# Sheet1.net
KiCad netlist of a schematic drawn in Altium Designer
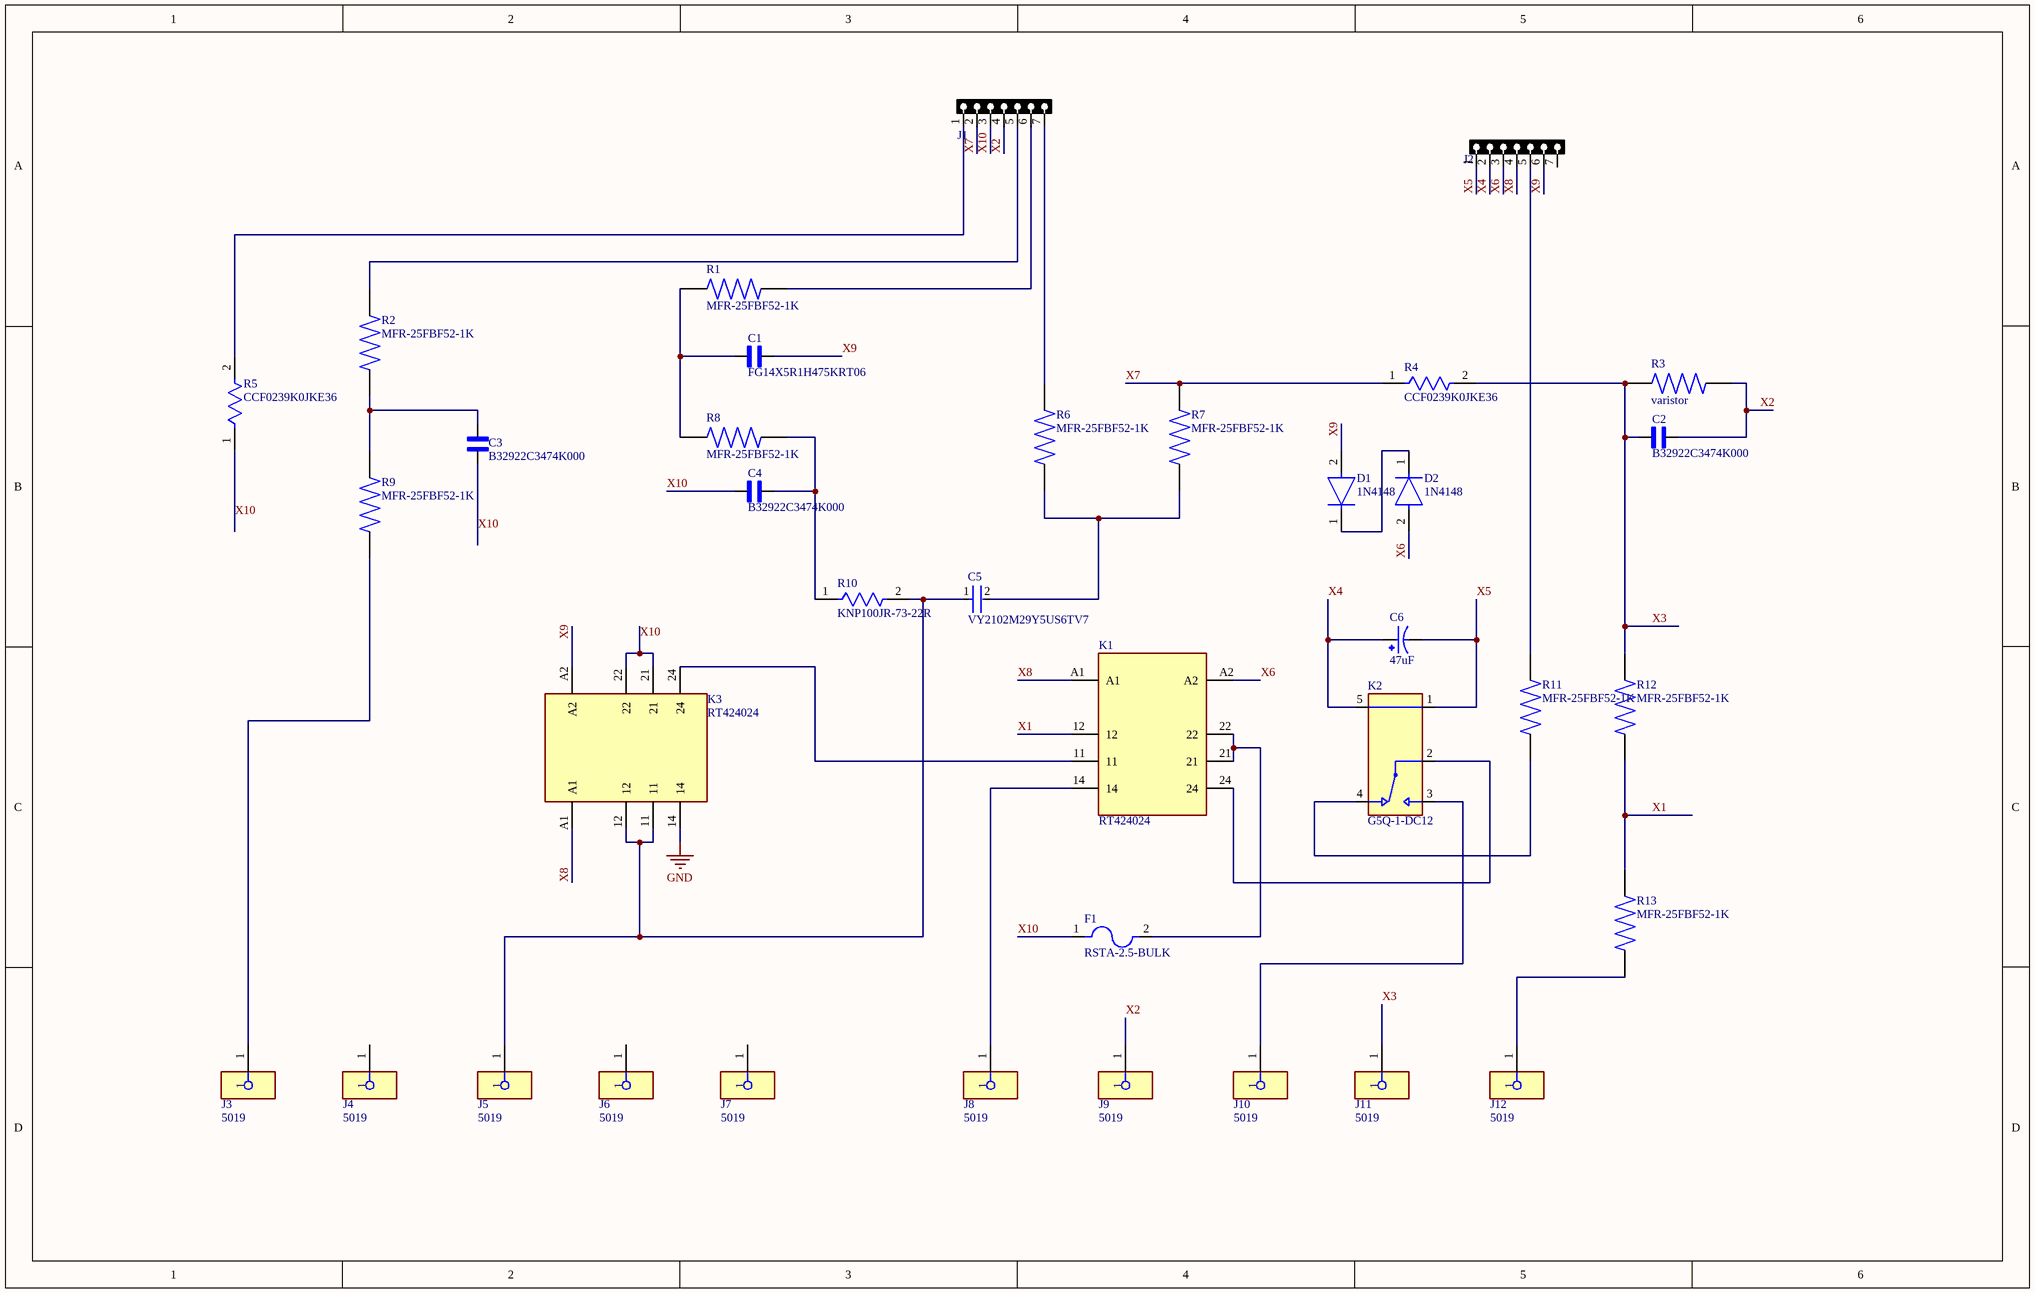
[diagram p0: Sheet1.SchDoc]

(export (version "E")
  (design (tool "Eeschema 10.0.6"))
  (components
    (comp (ref "C1")
      (value "FG14X5R1H475KRT06")
      (footprint "CAPRB250W50L450T300H550")
      (description "4.7 ÂµF Â±10% 50V Ceramic Capacitor X5R Radial")
      (fields (field (name "MF") "TDK"))
      (libsource (lib "FG14X5R1H475KRT06") (part "FG14X5R1H475KRT06"))
    )
    (comp (ref "C2")
      (value "B32922C3474K000")
      (footprint "CAPRR1500W80L1800T900H1750")
      (description "Safety Capacitor, 0.47 uF, 305 VAC, Â± 10%, X2, Metallized PP, Radial Box - 2 Pin, Through Hole")
      (fields (field (name "MF") "TDK"))
      (libsource (lib "") (part "B32922C3474K000_1"))
    )
    (comp (ref "C3")
      (value "B32922C3474K000")
      (footprint "CAPRR1500W80L1800T900H1750")
      (description "Safety Capacitor, 0.47 uF, 305 VAC, Â± 10%, X2, Metallized PP, Radial Box - 2 Pin, Through Hole")
      (fields (field (name "MF") "TDK"))
      (libsource (lib "B32922C3474K000") (part "B32922C3474K000"))
    )
    (comp (ref "C4")
      (value "B32922C3474K000")
      (footprint "CAPRR1500W80L1800T900H1750")
      (description "Safety Capacitor, 0.47 uF, 305 VAC, Â± 10%, X2, Metallized PP, Radial Box - 2 Pin, Through Hole")
      (fields (field (name "MF") "TDK"))
      (libsource (lib "") (part "B32922C3474K000_1"))
    )
    (comp (ref "C5")
      (value "VY2102M29Y5US6TV7")
      (footprint "FP-VY2102M29Y5US6TV7-MFG")
      (fields (field (name "VOLTAGE") "300V") (field (name "TOLERANCE") "20%"))
      (libsource (lib "Altium Content Vault") (part "11868f565c42a9108669ba33697ecf6"))
    )
    (comp (ref "C6")
      (value "47uF")
      (footprint "CAPPRD500W50D630H1120")
      (description "Cap Aluminum Lytic 47uF 63V 20% (6.3 X 11.2mm) Radial 5mm 120mA 1000h 105Â°C Automotive Ammo")
      (fields (field (name "MF") "Panasonic") (field (name "MP") "ECA1JHG470B"))
      (libsource (lib "ECA1JHG470B") (part "ECA1JHG470B"))
    )
    (comp (ref "D1")
      (value "1N4148")
      (footprint "FP-017AG-MFG")
      (description "DIODE GEN PURP 100V 200MA DO35")
      (fields (field (name "VOLTAGE") "100V"))
      (libsource (lib "Altium Content Vault") (part "d7152d700b627762746794eb795d46e"))
    )
    (comp (ref "D2")
      (value "1N4148")
      (footprint "FP-017AG-MFG")
      (description "DIODE GEN PURP 100V 200MA DO35")
      (fields (field (name "VOLTAGE") "100V"))
      (libsource (lib "Altium Content Vault") (part "d7152d700b627762746794eb795d46e"))
    )
    (comp (ref "F1")
      (value "RSTA-2.5-BULK")
      (footprint "FUSE_RST-1-BULK")
      (description "2.5 A 250 V AC 63 V DC Fuse Board Mount (Cartridge Style Excluded) Through Hole Radial, Box")
      (fields (field (name "MF") "Bel Fuse") (field (name "MP") "RSTA 2.5 BULK"))
      (libsource (lib "RSTA-2.5-BULK") (part "RSTA-2.5-BULK"))
    )
    (comp (ref "J1")
      (value "HDR1X7")
      (footprint "HDRMINI_F_1X7")
      (description "CONN, HEADER, Female, pitch: 1.27mm, 7POS")
      (libsource (lib "conn_header_1.27mm_st") (part "HDRMINI_F_1X7"))
    )
    (comp (ref "J2")
      (value "HDR1X7")
      (footprint "HDRMINI_F_1X7")
      (description "CONN, HEADER, Female, pitch: 1.27mm, 7POS")
      (libsource (lib "conn_header_1.27mm_st") (part "HDRMINI_F_1X7"))
    )
    (comp (ref "J3")
      (value "5019")
      (footprint "FP-5019-MFG")
      (libsource (lib "Altium Content Vault") (part "98815daf2f2c152b0c43f5ab9800df6"))
    )
    (comp (ref "J4")
      (value "5019")
      (footprint "FP-5019-MFG")
      (libsource (lib "Altium Content Vault") (part "98815daf2f2c152b0c43f5ab9800df6"))
    )
    (comp (ref "J5")
      (value "5019")
      (footprint "FP-5019-MFG")
      (libsource (lib "Altium Content Vault") (part "98815daf2f2c152b0c43f5ab9800df6"))
    )
    (comp (ref "J6")
      (value "5019")
      (footprint "FP-5019-MFG")
      (libsource (lib "Altium Content Vault") (part "98815daf2f2c152b0c43f5ab9800df6"))
    )
    (comp (ref "J7")
      (value "5019")
      (footprint "FP-5019-MFG")
      (libsource (lib "Altium Content Vault") (part "98815daf2f2c152b0c43f5ab9800df6"))
    )
    (comp (ref "J8")
      (value "5019")
      (footprint "FP-5019-MFG")
      (libsource (lib "Altium Content Vault") (part "98815daf2f2c152b0c43f5ab9800df6"))
    )
    (comp (ref "J9")
      (value "5019")
      (footprint "FP-5019-MFG")
      (libsource (lib "Altium Content Vault") (part "98815daf2f2c152b0c43f5ab9800df6"))
    )
    (comp (ref "J10")
      (value "5019")
      (footprint "FP-5019-MFG")
      (libsource (lib "Altium Content Vault") (part "98815daf2f2c152b0c43f5ab9800df6"))
    )
    (comp (ref "J11")
      (value "5019")
      (footprint "FP-5019-MFG")
      (libsource (lib "Altium Content Vault") (part "98815daf2f2c152b0c43f5ab9800df6"))
    )
    (comp (ref "J12")
      (value "5019")
      (footprint "FP-5019-MFG")
      (libsource (lib "Altium Content Vault") (part "98815daf2f2c152b0c43f5ab9800df6"))
    )
    (comp (ref "K1")
      (value "RT424024")
      (footprint "RELAY_RT424024")
      (description "General Purpose Relay DPDT (2 Form C) 24VDC Coil Through Hole")
      (fields (field (name "MF") "TE Connectivity"))
      (libsource (lib "RT424024") (part "RT424024"))
    )
    (comp (ref "K2")
      (value "G5Q-1-DC12")
      (footprint "RELAY_G5Q-1-DC12")
      (description "General Purpose Relay SPDT _1 Form C_ 12VDC Coil Through Hole")
      (fields (field (name "MF") "Omron Electronics"))
      (libsource (lib "G5Q-1-DC12") (part "G5Q-1-DC12"))
    )
    (comp (ref "K3")
      (value "RT424024")
      (footprint "RELAY_RT424024")
      (description "General Purpose Relay DPDT (2 Form C) 24VDC Coil Through Hole")
      (fields (field (name "MF") "TE Connectivity"))
      (libsource (lib "") (part "RT424024_1"))
    )
    (comp (ref "R1")
      (value "MFR-25FBF52-1K")
      (footprint "RESAD1100W55L680D260")
      (description "1.07 kOhms Â±1% 0.25W, 1/4W Through Hole Resistor Axial - Metal Film")
      (fields (field (name "MF") "Yageo"))
      (libsource (lib "MFR-25FBF52-1K") (part "MFR-25FBF52-1K"))
    )
    (comp (ref "R2")
      (value "MFR-25FBF52-1K")
      (footprint "RESAD1100W55L680D260")
      (description "1.07 kOhms Â±1% 0.25W, 1/4W Through Hole Resistor Axial - Metal Film")
      (fields (field (name "MF") "Yageo"))
      (libsource (lib "MFR-25FBF52-1K") (part "MFR-25FBF52-1K"))
    )
    (comp (ref "R3")
      (value "varistor")
      (footprint "RESAD1100W55L680D260")
      (description "1.07 kOhms Â±1% 0.25W, 1/4W Through Hole Resistor Axial - Metal Film")
      (fields (field (name "MF") "Yageo") (field (name "MP") "MFR-25FBF52-1K"))
      (libsource (lib "MFR-25FBF52-1K") (part "MFR-25FBF52-1K"))
    )
    (comp (ref "R4")
      (value "CCF0239K0JKE36")
      (footprint "FP-CCF02-MFG")
      (description "Metal Film Resistors - Through Hole")
      (fields
        (field (name "OCTOPART") "https://octopart.com/ccf0239k0jke36-vishay-98146781")
        (field (name "TOLERANCE") "5%")
      )
      (libsource (lib "Altium Content Vault") (part "1029c3af85768c4190bb7ad29bc67b5"))
    )
    (comp (ref "R5")
      (value "CCF0239K0JKE36")
      (footprint "FP-CCF02-MFG")
      (description "Metal Film Resistors - Through Hole")
      (fields
        (field (name "OCTOPART") "https://octopart.com/ccf0239k0jke36-vishay-98146781")
        (field (name "TOLERANCE") "5%")
      )
      (libsource (lib "Altium Content Vault") (part "1029c3af85768c4190bb7ad29bc67b5"))
    )
    (comp (ref "R6")
      (value "MFR-25FBF52-1K")
      (footprint "RESAD1100W55L680D260")
      (description "1.07 kOhms Â±1% 0.25W, 1/4W Through Hole Resistor Axial - Metal Film")
      (fields (field (name "MF") "Yageo"))
      (libsource (lib "MFR-25FBF52-1K") (part "MFR-25FBF52-1K"))
    )
    (comp (ref "R7")
      (value "MFR-25FBF52-1K")
      (footprint "RESAD1100W55L680D260")
      (description "1.07 kOhms Â±1% 0.25W, 1/4W Through Hole Resistor Axial - Metal Film")
      (fields (field (name "MF") "Yageo"))
      (libsource (lib "MFR-25FBF52-1K") (part "MFR-25FBF52-1K"))
    )
    (comp (ref "R8")
      (value "MFR-25FBF52-1K")
      (footprint "RESAD1100W55L680D260")
      (description "1.07 kOhms Â±1% 0.25W, 1/4W Through Hole Resistor Axial - Metal Film")
      (fields (field (name "MF") "Yageo"))
      (libsource (lib "MFR-25FBF52-1K") (part "MFR-25FBF52-1K"))
    )
    (comp (ref "R9")
      (value "MFR-25FBF52-1K")
      (footprint "RESAD1100W55L680D260")
      (description "1.07 kOhms Â±1% 0.25W, 1/4W Through Hole Resistor Axial - Metal Film")
      (fields (field (name "MF") "Yageo"))
      (libsource (lib "MFR-25FBF52-1K") (part "MFR-25FBF52-1K"))
    )
    (comp (ref "R10")
      (value "KNP100JR-73-22R")
      (footprint "FP-KNP100-MFG")
      (description "RES 22 OHM 1W 5% AXIAL")
      (fields
        (field (name "OCTOPART") "https://octopart.com/knp100jr-73-22r-yageo-19031610")
        (field (name "MANUFACTURER") "Yageo")
      )
      (libsource (lib "Altium Content Vault") (part "1029c3af85768c4190bb7ad29bc67b5"))
    )
    (comp (ref "R11")
      (value "MFR-25FBF52-1K")
      (footprint "RESAD1100W55L680D260")
      (description "1.07 kOhms Â±1% 0.25W, 1/4W Through Hole Resistor Axial - Metal Film")
      (fields (field (name "MF") "Yageo"))
      (libsource (lib "MFR-25FBF52-1K") (part "MFR-25FBF52-1K"))
    )
    (comp (ref "R12")
      (value "MFR-25FBF52-1K")
      (footprint "RESAD1100W55L680D260")
      (description "1.07 kOhms Â±1% 0.25W, 1/4W Through Hole Resistor Axial - Metal Film")
      (fields (field (name "MF") "Yageo"))
      (libsource (lib "MFR-25FBF52-1K") (part "MFR-25FBF52-1K"))
    )
    (comp (ref "R13")
      (value "MFR-25FBF52-1K")
      (footprint "RESAD1100W55L680D260")
      (description "1.07 kOhms Â±1% 0.25W, 1/4W Through Hole Resistor Axial - Metal Film")
      (fields (field (name "MF") "Yageo"))
      (libsource (lib "MFR-25FBF52-1K") (part "MFR-25FBF52-1K"))
    )
  )
  (nets
    (net (code "1") (name "/X1") (class "Default")
      (node (ref "K1") (pin "12") (pinfunction "12_12") (pintype "passive"))
      (node (ref "R12") (pin "1") (pinfunction "1_1") (pintype "passive"))
      (node (ref "R13") (pin "2") (pinfunction "2_2") (pintype "passive"))
    )
    (net (code "2") (name "/X2") (class "Default")
      (node (ref "C2") (pin "2") (pinfunction "2_2") (pintype "passive"))
      (node (ref "J1") (pin "4") (pinfunction "4_4") (pintype "passive"))
      (node (ref "J9") (pin "1") (pinfunction "1_1") (pintype "passive"))
      (node (ref "R3") (pin "1") (pinfunction "1_1") (pintype "passive"))
    )
    (net (code "3") (name "/X3") (class "Default")
      (node (ref "C2") (pin "1") (pinfunction "1_1") (pintype "passive"))
      (node (ref "J11") (pin "1") (pinfunction "1_1") (pintype "passive"))
      (node (ref "R12") (pin "2") (pinfunction "2_2") (pintype "passive"))
      (node (ref "R3") (pin "2") (pinfunction "2_2") (pintype "passive"))
      (node (ref "R4") (pin "2") (pinfunction "2_2") (pintype "passive"))
    )
    (net (code "4") (name "/X4") (class "Default")
      (node (ref "C6") (pin "P") (pinfunction "P_P") (pintype "passive"))
      (node (ref "J2") (pin "2") (pinfunction "2_2") (pintype "passive"))
      (node (ref "K2") (pin "5") (pinfunction "5_5") (pintype "passive"))
    )
    (net (code "5") (name "/X5") (class "Default")
      (node (ref "C6") (pin "N") (pinfunction "N_N") (pintype "passive"))
      (node (ref "J2") (pin "1") (pinfunction "1_1") (pintype "passive"))
      (node (ref "K2") (pin "1") (pinfunction "1_1") (pintype "passive"))
    )
    (net (code "6") (name "/X6") (class "Default")
      (node (ref "D2") (pin "2") (pinfunction "A_2") (pintype "passive"))
      (node (ref "J2") (pin "3") (pinfunction "3_3") (pintype "passive"))
      (node (ref "K1") (pin "A2") (pinfunction "A2_A2") (pintype "passive"))
    )
    (net (code "7") (name "/X7") (class "Default")
      (node (ref "J1") (pin "2") (pinfunction "2_2") (pintype "passive"))
      (node (ref "R4") (pin "1") (pinfunction "1_1") (pintype "passive"))
      (node (ref "R7") (pin "2") (pinfunction "2_2") (pintype "passive"))
    )
    (net (code "8") (name "/X8") (class "Default")
      (node (ref "J2") (pin "4") (pinfunction "4_4") (pintype "passive"))
      (node (ref "K1") (pin "A1") (pinfunction "A1_A1") (pintype "passive"))
      (node (ref "K3") (pin "A1") (pinfunction "A1_A1") (pintype "passive"))
    )
    (net (code "9") (name "/X9") (class "Default")
      (node (ref "C1") (pin "2") (pinfunction "2_2") (pintype "passive"))
      (node (ref "D1") (pin "2") (pinfunction "A_2") (pintype "passive"))
      (node (ref "J2") (pin "6") (pinfunction "6_6") (pintype "passive"))
      (node (ref "K3") (pin "A2") (pinfunction "A2_A2") (pintype "passive"))
    )
    (net (code "10") (name "/X10") (class "Default")
      (node (ref "C3") (pin "1") (pinfunction "1_1") (pintype "passive"))
      (node (ref "C4") (pin "1") (pinfunction "1_1") (pintype "passive"))
      (node (ref "F1") (pin "1") (pinfunction "1_1") (pintype "passive"))
      (node (ref "J1") (pin "3") (pinfunction "3_3") (pintype "passive"))
      (node (ref "K3") (pin "21") (pinfunction "21_21") (pintype "passive"))
      (node (ref "K3") (pin "22") (pinfunction "22_22") (pintype "passive"))
      (node (ref "R5") (pin "1") (pinfunction "1_1") (pintype "passive"))
    )
    (net (code "11") (name "GND") (class "Default")
      (node (ref "K3") (pin "14") (pinfunction "14_14") (pintype "passive"))
    )
    (net (code "12") (name "Net-(C1-Pad1)") (class "Default")
      (node (ref "C1") (pin "1") (pinfunction "1_1") (pintype "passive"))
      (node (ref "R1") (pin "2") (pinfunction "2_2") (pintype "passive"))
      (node (ref "R8") (pin "2") (pinfunction "2_2") (pintype "passive"))
    )
    (net (code "13") (name "Net-(C3-Pad2)") (class "Default")
      (node (ref "C3") (pin "2") (pinfunction "2_2") (pintype "passive"))
      (node (ref "R2") (pin "1") (pinfunction "1_1") (pintype "passive"))
      (node (ref "R9") (pin "2") (pinfunction "2_2") (pintype "passive"))
    )
    (net (code "14") (name "Net-(C4-Pad2)") (class "Default")
      (node (ref "C4") (pin "2") (pinfunction "2_2") (pintype "passive"))
      (node (ref "R10") (pin "1") (pinfunction "1_1") (pintype "passive"))
      (node (ref "R8") (pin "1") (pinfunction "1_1") (pintype "passive"))
    )
    (net (code "15") (name "Net-(C5-Pad1)") (class "Default")
      (node (ref "C5") (pin "1") (pinfunction "1_1") (pintype "passive"))
      (node (ref "J5") (pin "1") (pinfunction "1_1") (pintype "passive"))
      (node (ref "K3") (pin "11") (pinfunction "11_11") (pintype "passive"))
      (node (ref "K3") (pin "12") (pinfunction "12_12") (pintype "passive"))
      (node (ref "R10") (pin "2") (pinfunction "2_2") (pintype "passive"))
    )
    (net (code "16") (name "Net-(C5-Pad2)") (class "Default")
      (node (ref "C5") (pin "2") (pinfunction "2_2") (pintype "passive"))
      (node (ref "R6") (pin "1") (pinfunction "1_1") (pintype "passive"))
      (node (ref "R7") (pin "1") (pinfunction "1_1") (pintype "passive"))
    )
    (net (code "17") (name "Net-(D1-C)") (class "Default")
      (node (ref "D1") (pin "1") (pinfunction "C_1") (pintype "passive"))
      (node (ref "D2") (pin "1") (pinfunction "C_1") (pintype "passive"))
    )
    (net (code "18") (name "Net-(F1-Pad2)") (class "Default")
      (node (ref "F1") (pin "2") (pinfunction "2_2") (pintype "passive"))
      (node (ref "K1") (pin "21") (pinfunction "21_21") (pintype "passive"))
      (node (ref "K1") (pin "22") (pinfunction "22_22") (pintype "passive"))
    )
    (net (code "19") (name "Net-(J1-Pad1)") (class "Default")
      (node (ref "J1") (pin "1") (pinfunction "1_1") (pintype "passive"))
      (node (ref "R5") (pin "2") (pinfunction "2_2") (pintype "passive"))
    )
    (net (code "20") (name "Net-(J1-Pad5)") (class "Default")
      (node (ref "J1") (pin "5") (pinfunction "5_5") (pintype "passive"))
      (node (ref "R2") (pin "2") (pinfunction "2_2") (pintype "passive"))
    )
    (net (code "21") (name "Net-(J1-Pad6)") (class "Default")
      (node (ref "J1") (pin "6") (pinfunction "6_6") (pintype "passive"))
      (node (ref "R1") (pin "1") (pinfunction "1_1") (pintype "passive"))
    )
    (net (code "22") (name "Net-(J1-Pad7)") (class "Default")
      (node (ref "J1") (pin "7") (pinfunction "7_7") (pintype "passive"))
      (node (ref "R6") (pin "2") (pinfunction "2_2") (pintype "passive"))
    )
    (net (code "23") (name "Net-(J2-Pad5)") (class "Default")
      (node (ref "J2") (pin "5") (pinfunction "5_5") (pintype "passive"))
      (node (ref "R11") (pin "2") (pinfunction "2_2") (pintype "passive"))
    )
    (net (code "24") (name "Net-(J3-Pad1)") (class "Default")
      (node (ref "J3") (pin "1") (pinfunction "1_1") (pintype "passive"))
      (node (ref "R9") (pin "1") (pinfunction "1_1") (pintype "passive"))
    )
    (net (code "25") (name "Net-(J8-Pad1)") (class "Default")
      (node (ref "J8") (pin "1") (pinfunction "1_1") (pintype "passive"))
      (node (ref "K1") (pin "14") (pinfunction "14_14") (pintype "passive"))
    )
    (net (code "26") (name "Net-(J10-Pad1)") (class "Default")
      (node (ref "J10") (pin "1") (pinfunction "1_1") (pintype "passive"))
      (node (ref "K2") (pin "3") (pinfunction "3_3") (pintype "passive"))
    )
    (net (code "27") (name "Net-(J12-Pad1)") (class "Default")
      (node (ref "J12") (pin "1") (pinfunction "1_1") (pintype "passive"))
      (node (ref "R13") (pin "1") (pinfunction "1_1") (pintype "passive"))
    )
    (net (code "28") (name "Net-(K1-Pad11)") (class "Default")
      (node (ref "K1") (pin "11") (pinfunction "11_11") (pintype "passive"))
      (node (ref "K3") (pin "24") (pinfunction "24_24") (pintype "passive"))
    )
    (net (code "29") (name "Net-(K1-Pad24)") (class "Default")
      (node (ref "K1") (pin "24") (pinfunction "24_24") (pintype "passive"))
      (node (ref "K2") (pin "2") (pinfunction "2_2") (pintype "passive"))
    )
    (net (code "30") (name "Net-(K2-Pad4)") (class "Default")
      (node (ref "K2") (pin "4") (pinfunction "4_4") (pintype "passive"))
      (node (ref "R11") (pin "1") (pinfunction "1_1") (pintype "passive"))
    )
    (net (code "31") (name "unconnected-(J2-Pad7)") (class "Default")
      (node (ref "J2") (pin "7") (pinfunction "7_7") (pintype "passive"))
    )
    (net (code "32") (name "unconnected-(J4-Pad1)") (class "Default")
      (node (ref "J4") (pin "1") (pinfunction "1_1") (pintype "passive"))
    )
    (net (code "33") (name "unconnected-(J6-Pad1)") (class "Default")
      (node (ref "J6") (pin "1") (pinfunction "1_1") (pintype "passive"))
    )
    (net (code "34") (name "unconnected-(J7-Pad1)") (class "Default")
      (node (ref "J7") (pin "1") (pinfunction "1_1") (pintype "passive"))
    )
  )
)
